# 12_WIFI_Module.net
KiCad netlist of a schematic drawn in Altium Designer
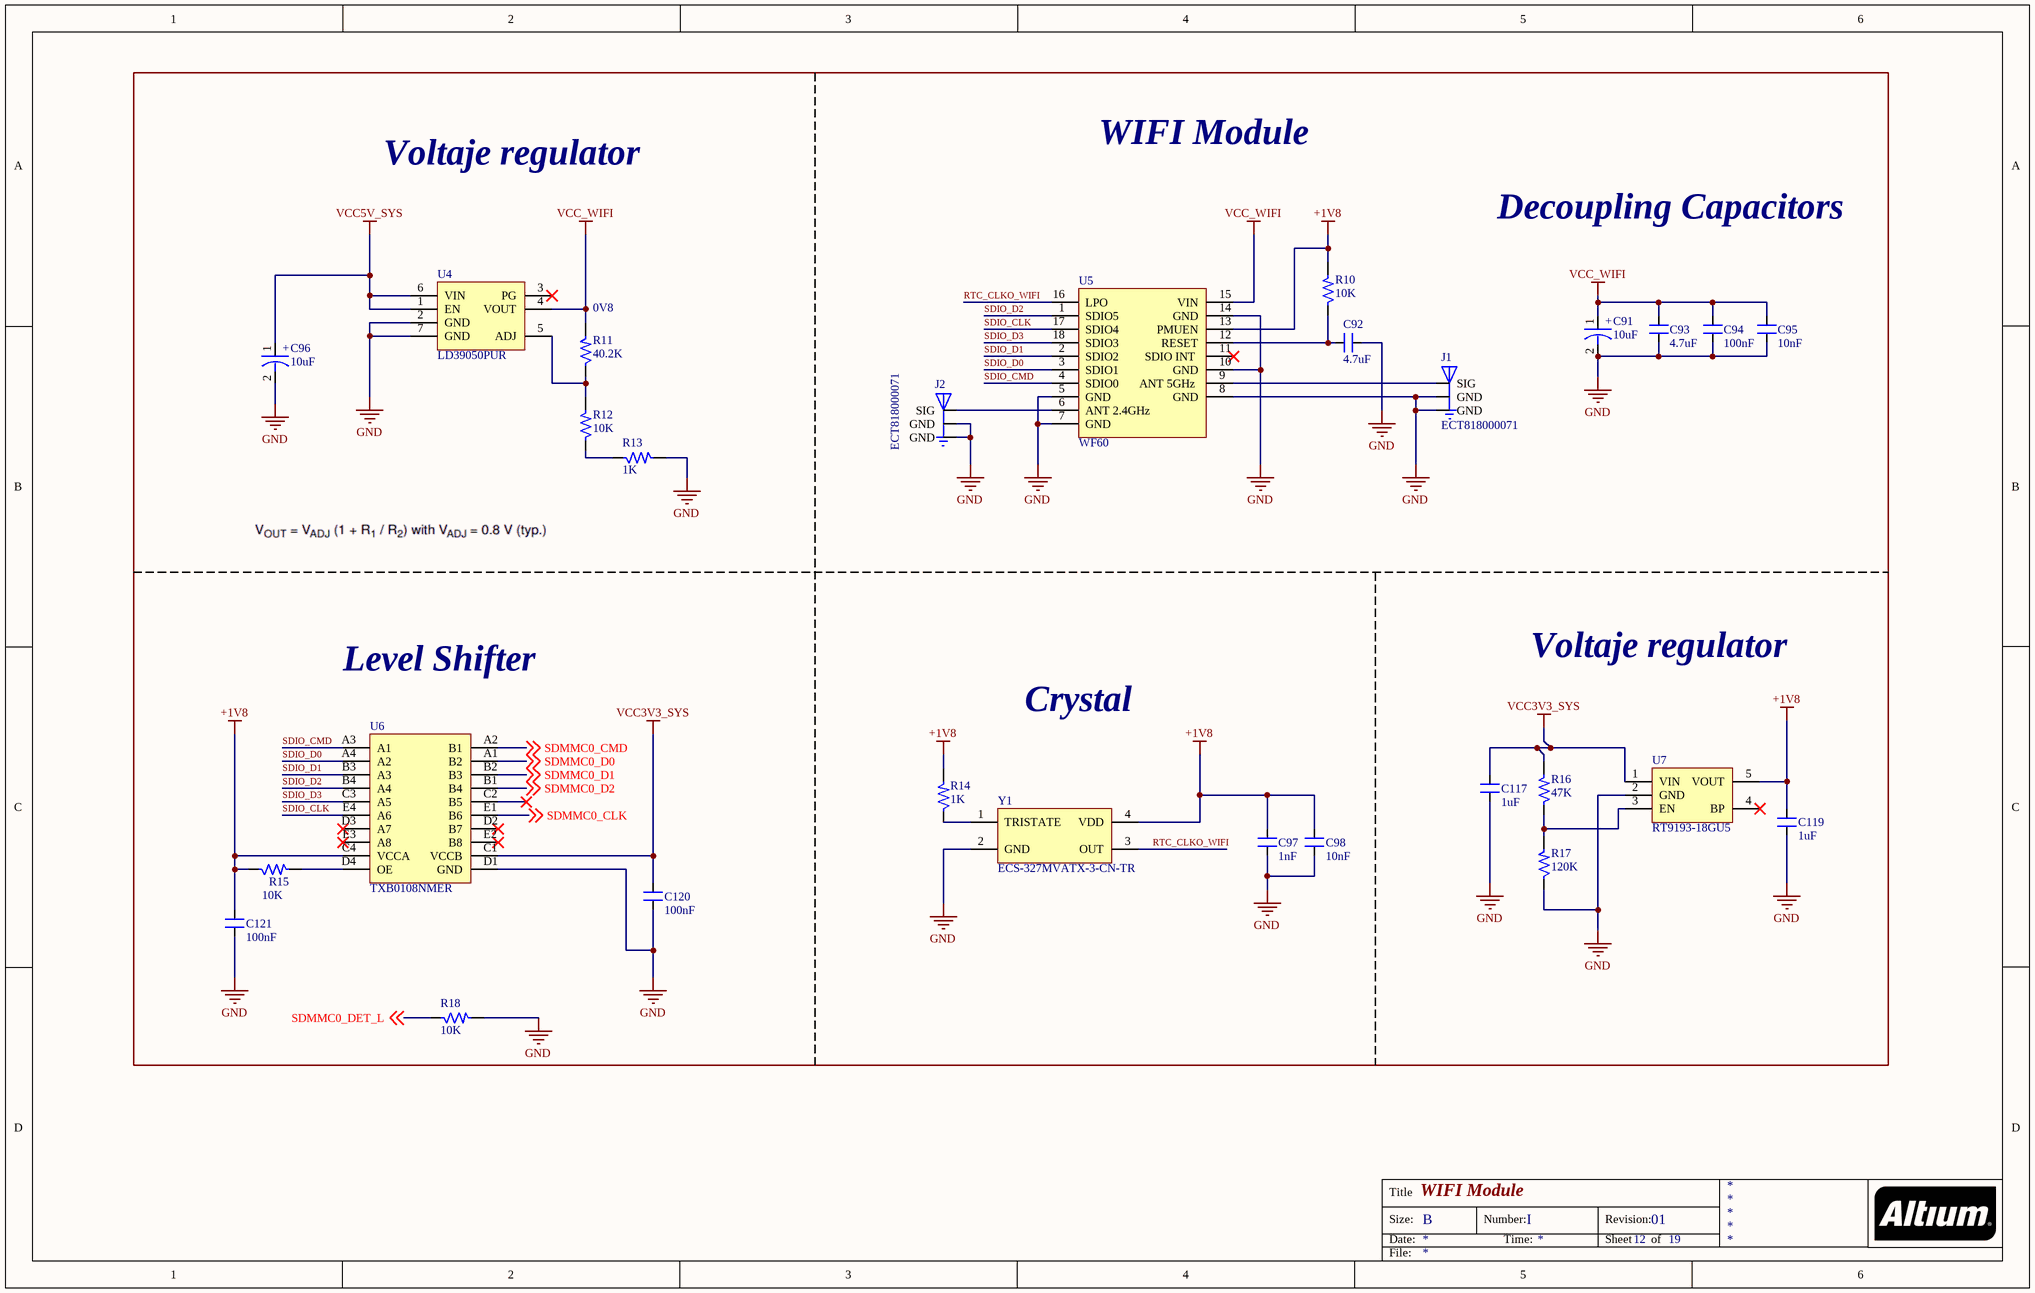
[diagram p0: [12] WIFI_Module.SchDoc]

(export (version "E")
  (design (tool "Eeschema 10.0.6"))
  (components
    (comp (ref "C91")
      (value "10uF")
      (footprint "CAP-T_1206")
      (description "10µF Molded Tantalum Capacitors 16V 1206 (3216 Metric) 3Ohm")
      (fields
        (field (name "MANUFACTURER") "AVX Corporation")
        (field (name "MANUFACTURER PART NUMBER") "TAJA106K016SNJ")
      )
      (libsource (lib "EsteemPCB_SOM_Course_intlib") (part "CAP-P_10uF-16V-10%-1206"))
    )
    (comp (ref "C92")
      (value "4.7uF")
      (footprint "CAP_0201")
      (description "4.7µF ±20% 6.3V Ceramic Capacitor X5R 0201 (0603 Metric)")
      (fields
        (field (name "MANUFACTURER") "Murata Electronics")
        (field (name "MANUFACTURER PART NUMBER") "GRM035R60J475ME15D")
      )
      (libsource (lib "EsteemPCB_SOM_Course_intlib") (part "CAP_4.7uF-6.3V-20%-0201"))
    )
    (comp (ref "C93")
      (value "4.7uF")
      (footprint "CAP_0402")
      (description "4.7µF ±10% 10V Ceramic Capacitor X5R 0402 (1005 Metric)")
      (fields
        (field (name "MANUFACTURER") "Samsung Electro-Mechanics")
        (field (name "MANUFACTURER PART NUMBER") "CL05A475KP5NRNC")
      )
      (libsource (lib "EsteemPCB_SOM_Course_intlib") (part "CAP_4.7uF-10V-10%-0402"))
    )
    (comp (ref "C94")
      (value "100nF")
      (footprint "CAP_0402")
      (description "0.1µF ±10% 25V Ceramic Capacitor X7R 0402 (1005 Metric)")
      (fields
        (field (name "MANUFACTURER") "Walsin Technology Corporation")
        (field (name "MANUFACTURER PART NUMBER") "0402B104K250CT")
      )
      (libsource (lib "EsteemPCB_SOM_Course_intlib") (part "CAP_100nF-25V-10%-0402"))
    )
    (comp (ref "C95")
      (value "10nF")
      (footprint "CAP_0402")
      (description "10000pF ±10% 10V Ceramic Capacitor X7R 0402 (1005 Metric)")
      (fields
        (field (name "MANUFACTURER") "AVX Corporation")
        (field (name "MANUFACTURER PART NUMBER") "0402ZC103KAT2A")
      )
      (libsource (lib "EsteemPCB_SOM_Course_intlib") (part "CAP_10nF-10V-10%-0402"))
    )
    (comp (ref "C96")
      (value "10uF")
      (footprint "CAP-T_1206")
      (description "10µF Molded Tantalum Capacitors 16V 1206 (3216 Metric) 3Ohm")
      (fields
        (field (name "MANUFACTURER") "AVX Corporation")
        (field (name "MANUFACTURER PART NUMBER") "TAJA106K016SNJ")
      )
      (libsource (lib "EsteemPCB_SOM_Course_intlib") (part "CAP-P_10uF-16V-10%-1206"))
    )
    (comp (ref "C97")
      (value "1nF")
      (footprint "CAP_0402")
      (description "1000pF ±10% 10V Ceramic Capacitor X7R 0402 (1005 Metric)")
      (fields
        (field (name "MANUFACTURER") "KEMET")
        (field (name "MANUFACTURER PART NUMBER") "C0402C102K8RACTU")
      )
      (libsource (lib "EsteemPCB_SOM_Course_intlib") (part "CAP_1nF-10V-10%-0402"))
    )
    (comp (ref "C98")
      (value "10nF")
      (footprint "CAP_0402")
      (description "10000pF ±10% 10V Ceramic Capacitor X7R 0402 (1005 Metric)")
      (fields
        (field (name "MANUFACTURER") "AVX Corporation")
        (field (name "MANUFACTURER PART NUMBER") "0402ZC103KAT2A")
      )
      (libsource (lib "EsteemPCB_SOM_Course_intlib") (part "CAP_10nF-10V-10%-0402"))
    )
    (comp (ref "C117")
      (value "1uF")
      (footprint "CAP_0201")
      (description "1µF ±20% 16V Ceramic Capacitor X5R 0201 (0603 Metric)")
      (fields
        (field (name "MANUFACTURER") "Samsung Electro-Mechanics")
        (field (name "MANUFACTURER PART NUMBER") "CL03A105MO3NRNH")
      )
      (libsource (lib "EsteemPCB_SOM_Course_intlib") (part "CAP_1uF-16V-10%-0201"))
    )
    (comp (ref "C119")
      (value "1uF")
      (footprint "CAP_0201")
      (description "1µF ±20% 16V Ceramic Capacitor X5R 0201 (0603 Metric)")
      (fields
        (field (name "MANUFACTURER") "Samsung Electro-Mechanics")
        (field (name "MANUFACTURER PART NUMBER") "CL03A105MO3NRNH")
      )
      (libsource (lib "EsteemPCB_SOM_Course_intlib") (part "CAP_1uF-16V-10%-0201"))
    )
    (comp (ref "C120")
      (value "100nF")
      (footprint "CAP_0201")
      (description "0.1µF ±10% 25V Ceramic Capacitor X5R 0201 (0603 Metric)")
      (fields
        (field (name "MANUFACTURER") "TDK Corporation")
        (field (name "MANUFACTURER PART NUMBER") "C0603X5R1E104K030BB")
      )
      (libsource (lib "EsteemPCB_SOM_Course_intlib") (part "CAP_100nF-25V-10%-0201"))
    )
    (comp (ref "C121")
      (value "100nF")
      (footprint "CAP_0201")
      (description "0.1µF ±10% 25V Ceramic Capacitor X5R 0201 (0603 Metric)")
      (fields
        (field (name "MANUFACTURER") "TDK Corporation")
        (field (name "MANUFACTURER PART NUMBER") "C0603X5R1E104K030BB")
      )
      (libsource (lib "EsteemPCB_SOM_Course_intlib") (part "CAP_100nF-25V-10%-0201"))
    )
    (comp (ref "J1")
      (value "ECT818000071")
      (footprint "CON3_UFL_116_SMD_ST")
      (description "SMD RF Connectors/Coaxial Connectors RoHS")
      (fields (field (name "MANUFACTURER") "ECT"))
      (libsource (lib "EsteemPCB_SOM_Course_intlib") (part "CON-PLG_3X1-ECT818000071-ST-SMD"))
    )
    (comp (ref "J2")
      (value "ECT818000071")
      (footprint "CON3_UFL_116_SMD_ST")
      (description "SMD RF Connectors/Coaxial Connectors RoHS")
      (fields (field (name "MANUFACTURER") "ECT"))
      (libsource (lib "EsteemPCB_SOM_Course_intlib") (part "CON-PLG_3X1-ECT818000071-ST-SMD"))
    )
    (comp (ref "R10")
      (value "10K")
      (footprint "RES_0201")
      (description "10 kOhms ±1% 0.05W, 1/20W Chip Resistor 0201 (0603 Metric) Thick Film")
      (fields
        (field (name "MANUFACTURER") "Stackpole Electronics Inc")
        (field (name "MANUFACTURER PART NUMBER") "RMCF0201FT10K0")
      )
      (libsource (lib "EsteemPCB_SOM_Course_intlib") (part "RES_10K-0.05W-1%-0201"))
    )
    (comp (ref "R11")
      (value "40.2K")
      (footprint "RES_0201")
      (fields
        (field (name "MANUFACTURER") "Yageo")
        (field (name "MANUFACTURER PART NUMBER") "AC0201FR-0740K2L")
      )
      (libsource (lib "EsteemPCB_SOM_Course_intlib") (part "RES_40.2K-0.05W-1%-0201"))
    )
    (comp (ref "R12")
      (value "10K")
      (footprint "RES_0201")
      (description "10 kOhms ±1% 0.05W, 1/20W Chip Resistor 0201 (0603 Metric) Thick Film")
      (fields
        (field (name "MANUFACTURER") "Stackpole Electronics Inc")
        (field (name "MANUFACTURER PART NUMBER") "RMCF0201FT10K0")
      )
      (libsource (lib "EsteemPCB_SOM_Course_intlib") (part "RES_10K-0.05W-1%-0201"))
    )
    (comp (ref "R13")
      (value "1K")
      (footprint "RES_0402")
      (description "1 kOhms ±1% 0.1W, 1/10W Chip Resistor 0402 (1005 Metric) Anti-Sulfur Thin Film")
      (fields
        (field (name "MANUFACTURER") "Vishay Beyschlag/Draloric/BC Components")
        (field (name "MANUFACTURER PART NUMBER") "MCS04020C1001FE000")
      )
      (libsource (lib "EsteemPCB_SOM_Course_intlib") (part "RES_1K-0.1W-1%-0402"))
    )
    (comp (ref "R14")
      (value "1K")
      (footprint "RES_0201")
      (description "10 kOhms ±1% 0.05W, 1/20W Chip Resistor 0201 (0603 Metric) Thick Film")
      (fields
        (field (name "MANUFACTURER") "Stackpole Electronics Inc")
        (field (name "MANUFACTURER PART NUMBER") "RMCF0201FT10K0")
      )
      (libsource (lib "EsteemPCB_SOM_Course_intlib") (part "RES_10K-0.05W-1%-0201"))
    )
    (comp (ref "R15")
      (value "10K")
      (footprint "RES_0201")
      (description "10 kOhms ±1% 0.05W, 1/20W Chip Resistor 0201 (0603 Metric) Thick Film")
      (fields
        (field (name "MANUFACTURER") "Stackpole Electronics Inc")
        (field (name "MANUFACTURER PART NUMBER") "RMCF0201FT10K0")
      )
      (libsource (lib "EsteemPCB_SOM_Course_intlib") (part "RES_10K-0.05W-1%-0201"))
    )
    (comp (ref "R16")
      (value "47K")
      (footprint "RES_0402")
      (description "47 kOhms ±1% 0.1W, 1/10W Chip Resistor 0402 (1005 Metric) Automotive AEC-Q200 Thick Film")
      (fields
        (field (name "MANUFACTURER") "Panasonic Electronic Components")
        (field (name "MANUFACTURER PART NUMBER") "ERJ-2RKF4702X")
      )
      (libsource (lib "EsteemPCB_SOM_Course_intlib") (part "RES_47K-0.1W-1%-0402"))
    )
    (comp (ref "R17")
      (value "120K")
      (footprint "RES_0402")
      (description "120 kOhms ±1% 0.1W, 1/10W Chip Resistor 0402 (1005 Metric) Anti-Sulfur Thin Film")
      (fields
        (field (name "MANUFACTURER") "Vishay Beyschlag/Draloric/BC Components")
        (field (name "MANUFACTURER PART NUMBER") "MCS04020C1203FE000")
      )
      (libsource (lib "EsteemPCB_SOM_Course_intlib") (part "RES_120K-0.1W-1%-0402"))
    )
    (comp (ref "R18")
      (value "10K")
      (footprint "RES_0201")
      (description "10 kOhms ±1% 0.05W, 1/20W Chip Resistor 0201 (0603 Metric) Thick Film")
      (fields
        (field (name "MANUFACTURER") "Stackpole Electronics Inc")
        (field (name "MANUFACTURER PART NUMBER") "RMCF0201FT10K0")
      )
      (libsource (lib "EsteemPCB_SOM_Course_intlib") (part "RES_10K-0.05W-1%-0201"))
    )
    (comp (ref "U4")
      (value "LD39050PUR")
      (footprint "DFN-6_37.4_165_33X15_SMD")
      (description "Adjustable 5.5V 0.8V 500mA DFN-6 Linear Voltage Regulators RoHS")
      (fields (field (name "MANUFACTURER") "STMicroelectronics"))
      (libsource (lib "EsteemPCB_SOM_Course_intlib") (part "REG_5.5V-0~5.1V-0.5A-2.55W-DFN-6"))
    )
    (comp (ref "U5")
      (value "WF60")
      (footprint "MOD_WF60")
      (description "Amp’ed RF Tech presents the WF60 WiFi dual\r\nband module: 802.11abgn.")
      (fields (field (name "MANUFACTURER") "Amp’ed"))
      (libsource (lib "EsteemPCB_SOM_Course_intlib") (part "MOD_WF60-SMD"))
    )
    (comp (ref "U6")
      (value "TXB0108NMER")
      (footprint "NFBGA_31.4_125.9X102.36")
      (fields (field (name "MANUFACTURER") "Texas Instruments"))
      (libsource (lib "EsteemPCB_SOM_Course_intlib") (part "IC_TXB0108NMER"))
    )
    (comp (ref "U7")
      (value "RT9193-18GU5")
      (footprint "SC70-5")
      (description "Linear Voltage Regulator IC 1 Output 300mA SC-70-5")
      (fields (field (name "MANUFACTURER") "Richtek USA Inc."))
      (libsource (lib "EsteemPCB_SOM_Course_intlib") (part "REG_1.8V-300mA-5.5V-SC70-5"))
    )
    (comp (ref "Y1")
      (value "ECS-327MVATX-3-CN-TR")
      (footprint "XTAL_57_35X31_SMD")
      (description "32.768kHz XO (Standard) CMOS Oscillator 1.6V ~ 3.6V Enable/Disable 4-SMD, No Lead")
      (fields (field (name "MANUFACTURER") "ECS INC"))
      (libsource (lib "EsteemPCB_SOM_Course_intlib") (part "XTAL_ECS-327MVATX-2-CN-TR"))
    )
  )
  (nets
    (net (code "1") (name "+1V8") (class "Default")
      (node (ref "C119") (pin "2") (pinfunction "2_2") (pintype "passive"))
      (node (ref "C121") (pin "2") (pinfunction "2_2") (pintype "passive"))
      (node (ref "C97") (pin "2") (pinfunction "2_2") (pintype "passive"))
      (node (ref "C98") (pin "2") (pinfunction "2_2") (pintype "passive"))
      (node (ref "R10") (pin "2") (pinfunction "2_2") (pintype "passive"))
      (node (ref "R14") (pin "2") (pinfunction "2_2") (pintype "passive"))
      (node (ref "R15") (pin "1") (pinfunction "1_1") (pintype "passive"))
      (node (ref "U5") (pin "13") (pinfunction "PMUEN_13") (pintype "passive"))
      (node (ref "U6") (pin "C4") (pinfunction "VCCA_C4") (pintype "passive"))
      (node (ref "U7") (pin "5") (pinfunction "VOUT_5") (pintype "passive"))
      (node (ref "Y1") (pin "4") (pinfunction "VDD_4") (pintype "passive"))
    )
    (net (code "2") (name "/RTC_CLKO_WIFI") (class "Default")
      (node (ref "U5") (pin "16") (pinfunction "LPO_16") (pintype "passive"))
      (node (ref "Y1") (pin "3") (pinfunction "OUT_3") (pintype "passive"))
    )
    (net (code "3") (name "/SDIO_CLK") (class "Default")
      (node (ref "U5") (pin "17") (pinfunction "SDIO4_17") (pintype "passive"))
      (node (ref "U6") (pin "E4") (pinfunction "A6_E4") (pintype "passive"))
    )
    (net (code "4") (name "/SDIO_CMD") (class "Default")
      (node (ref "U5") (pin "4") (pinfunction "SDIO0_4") (pintype "passive"))
      (node (ref "U6") (pin "A3") (pinfunction "A1_A3") (pintype "passive"))
    )
    (net (code "5") (name "/SDIO_D0") (class "Default")
      (node (ref "U5") (pin "3") (pinfunction "SDIO1_3") (pintype "passive"))
      (node (ref "U6") (pin "A4") (pinfunction "A2_A4") (pintype "passive"))
    )
    (net (code "6") (name "/SDIO_D1") (class "Default")
      (node (ref "U5") (pin "2") (pinfunction "SDIO2_2") (pintype "passive"))
      (node (ref "U6") (pin "B3") (pinfunction "A3_B3") (pintype "passive"))
    )
    (net (code "7") (name "/SDIO_D2") (class "Default")
      (node (ref "U5") (pin "1") (pinfunction "SDIO5_1") (pintype "passive"))
      (node (ref "U6") (pin "B4") (pinfunction "A4_B4") (pintype "passive"))
    )
    (net (code "8") (name "/SDIO_D3") (class "Default")
      (node (ref "U5") (pin "18") (pinfunction "SDIO3_18") (pintype "passive"))
      (node (ref "U6") (pin "C3") (pinfunction "A5_C3") (pintype "passive"))
    )
    (net (code "9") (name "GND") (class "Default")
      (node (ref "C117") (pin "1") (pinfunction "1_1") (pintype "passive"))
      (node (ref "C119") (pin "1") (pinfunction "1_1") (pintype "passive"))
      (node (ref "C120") (pin "1") (pinfunction "1_1") (pintype "passive"))
      (node (ref "C121") (pin "1") (pinfunction "1_1") (pintype "passive"))
      (node (ref "C91") (pin "2") (pinfunction "2_2") (pintype "passive"))
      (node (ref "C92") (pin "2") (pinfunction "2_2") (pintype "passive"))
      (node (ref "C93") (pin "1") (pinfunction "1_1") (pintype "passive"))
      (node (ref "C94") (pin "1") (pinfunction "1_1") (pintype "passive"))
      (node (ref "C95") (pin "1") (pinfunction "1_1") (pintype "passive"))
      (node (ref "C96") (pin "2") (pinfunction "2_2") (pintype "passive"))
      (node (ref "C97") (pin "1") (pinfunction "1_1") (pintype "passive"))
      (node (ref "C98") (pin "1") (pinfunction "1_1") (pintype "passive"))
      (node (ref "J1") (pin "1") (pinfunction "GND_1") (pintype "passive"))
      (node (ref "J1") (pin "3") (pinfunction "GND_3") (pintype "passive"))
      (node (ref "J2") (pin "1") (pinfunction "GND_1") (pintype "passive"))
      (node (ref "J2") (pin "3") (pinfunction "GND_3") (pintype "passive"))
      (node (ref "R13") (pin "2") (pinfunction "2_2") (pintype "passive"))
      (node (ref "R17") (pin "1") (pinfunction "1_1") (pintype "passive"))
      (node (ref "R18") (pin "2") (pinfunction "2_2") (pintype "passive"))
      (node (ref "U4") (pin "2") (pinfunction "GND_2") (pintype "passive"))
      (node (ref "U4") (pin "7") (pinfunction "GND_7") (pintype "passive"))
      (node (ref "U5") (pin "10") (pinfunction "GND_10") (pintype "passive"))
      (node (ref "U5") (pin "14") (pinfunction "GND_14") (pintype "passive"))
      (node (ref "U5") (pin "5") (pinfunction "GND_5") (pintype "passive"))
      (node (ref "U5") (pin "7") (pinfunction "GND_7") (pintype "passive"))
      (node (ref "U5") (pin "8") (pinfunction "GND_8") (pintype "passive"))
      (node (ref "U6") (pin "D1") (pinfunction "GND_D1") (pintype "passive"))
      (node (ref "U7") (pin "2") (pinfunction "GND_2") (pintype "passive"))
      (node (ref "Y1") (pin "2") (pinfunction "GND_2") (pintype "passive"))
    )
    (net (code "10") (name "Net-(J1-SIG)") (class "Default")
      (node (ref "J1") (pin "2") (pinfunction "SIG_2") (pintype "passive"))
      (node (ref "U5") (pin "9") (pinfunction "ANT_5GHz_9") (pintype "passive"))
    )
    (net (code "11") (name "Net-(J2-SIG)") (class "Default")
      (node (ref "J2") (pin "2") (pinfunction "SIG_2") (pintype "passive"))
      (node (ref "U5") (pin "6") (pinfunction "ANT_2.4GHz_6") (pintype "passive"))
    )
    (net (code "12") (name "Net-(R12-Pad1)") (class "Default")
      (node (ref "R12") (pin "1") (pinfunction "1_1") (pintype "passive"))
      (node (ref "R13") (pin "1") (pinfunction "1_1") (pintype "passive"))
    )
    (net (code "13") (name "Net-(U4-ADJ)") (class "Default")
      (node (ref "R11") (pin "1") (pinfunction "1_1") (pintype "passive"))
      (node (ref "R12") (pin "2") (pinfunction "2_2") (pintype "passive"))
      (node (ref "U4") (pin "5") (pinfunction "ADJ_5") (pintype "passive"))
    )
    (net (code "14") (name "Net-(U5-RESET)") (class "Default")
      (node (ref "C92") (pin "1") (pinfunction "1_1") (pintype "passive"))
      (node (ref "R10") (pin "1") (pinfunction "1_1") (pintype "passive"))
      (node (ref "U5") (pin "12") (pinfunction "RESET_12") (pintype "passive"))
    )
    (net (code "15") (name "Net-(U6-OE)") (class "Default")
      (node (ref "R15") (pin "2") (pinfunction "2_2") (pintype "passive"))
      (node (ref "U6") (pin "D4") (pinfunction "OE_D4") (pintype "passive"))
    )
    (net (code "16") (name "Net-(U7-EN)") (class "Default")
      (node (ref "R16") (pin "1") (pinfunction "1_1") (pintype "passive"))
      (node (ref "R17") (pin "2") (pinfunction "2_2") (pintype "passive"))
      (node (ref "U7") (pin "3") (pinfunction "EN_3") (pintype "passive"))
    )
    (net (code "17") (name "Net-(Y1-TRISTATE)") (class "Default")
      (node (ref "R14") (pin "1") (pinfunction "1_1") (pintype "passive"))
      (node (ref "Y1") (pin "1") (pinfunction "TRISTATE_1") (pintype "passive"))
    )
    (net (code "18") (name "SDMMC0_CLK") (class "Default")
      (node (ref "U6") (pin "E1") (pinfunction "B6_E1") (pintype "passive"))
    )
    (net (code "19") (name "SDMMC0_CMD") (class "Default")
      (node (ref "U6") (pin "A2") (pinfunction "B1_A2") (pintype "passive"))
    )
    (net (code "20") (name "SDMMC0_D0") (class "Default")
      (node (ref "U6") (pin "A1") (pinfunction "B2_A1") (pintype "passive"))
    )
    (net (code "21") (name "SDMMC0_D1") (class "Default")
      (node (ref "U6") (pin "B2") (pinfunction "B3_B2") (pintype "passive"))
    )
    (net (code "22") (name "SDMMC0_D2") (class "Default")
      (node (ref "U6") (pin "B1") (pinfunction "B4_B1") (pintype "passive"))
    )
    (net (code "23") (name "SDMMC0_DET_L") (class "Default")
      (node (ref "R18") (pin "1") (pinfunction "1_1") (pintype "passive"))
    )
    (net (code "24") (name "VCC3V3_SYS") (class "Default")
      (node (ref "C117") (pin "2") (pinfunction "2_2") (pintype "passive"))
      (node (ref "C120") (pin "2") (pinfunction "2_2") (pintype "passive"))
      (node (ref "R16") (pin "2") (pinfunction "2_2") (pintype "passive"))
      (node (ref "U6") (pin "C1") (pinfunction "VCCB_C1") (pintype "passive"))
      (node (ref "U7") (pin "1") (pinfunction "VIN_1") (pintype "passive"))
    )
    (net (code "25") (name "VCC5V_SYS") (class "Default")
      (node (ref "C96") (pin "1") (pinfunction "1_1") (pintype "passive"))
      (node (ref "U4") (pin "1") (pinfunction "EN_1") (pintype "passive"))
      (node (ref "U4") (pin "6") (pinfunction "VIN_6") (pintype "passive"))
    )
    (net (code "26") (name "VCC_WIFI") (class "Default")
      (node (ref "C91") (pin "1") (pinfunction "1_1") (pintype "passive"))
      (node (ref "C93") (pin "2") (pinfunction "2_2") (pintype "passive"))
      (node (ref "C94") (pin "2") (pinfunction "2_2") (pintype "passive"))
      (node (ref "C95") (pin "2") (pinfunction "2_2") (pintype "passive"))
      (node (ref "R11") (pin "2") (pinfunction "2_2") (pintype "passive"))
      (node (ref "U4") (pin "4") (pinfunction "VOUT_4") (pintype "passive"))
      (node (ref "U5") (pin "15") (pinfunction "VIN_15") (pintype "passive"))
    )
    (net (code "27") (name "unconnected-(U4-PG-Pad3)") (class "Default")
      (node (ref "U4") (pin "3") (pinfunction "PG_3") (pintype "passive+no_connect"))
    )
    (net (code "28") (name "unconnected-(U5-SDIO_INT-Pad11)") (class "Default")
      (node (ref "U5") (pin "11") (pinfunction "SDIO_INT_11") (pintype "passive+no_connect"))
    )
    (net (code "29") (name "unconnected-(U6-A7-PadD3)") (class "Default")
      (node (ref "U6") (pin "D3") (pinfunction "A7_D3") (pintype "passive+no_connect"))
    )
    (net (code "30") (name "unconnected-(U6-A8-PadE3)") (class "Default")
      (node (ref "U6") (pin "E3") (pinfunction "A8_E3") (pintype "passive+no_connect"))
    )
    (net (code "31") (name "unconnected-(U6-B5-PadC2)") (class "Default")
      (node (ref "U6") (pin "C2") (pinfunction "B5_C2") (pintype "passive+no_connect"))
    )
    (net (code "32") (name "unconnected-(U6-B7-PadD2)") (class "Default")
      (node (ref "U6") (pin "D2") (pinfunction "B7_D2") (pintype "passive+no_connect"))
    )
    (net (code "33") (name "unconnected-(U6-B8-PadE2)") (class "Default")
      (node (ref "U6") (pin "E2") (pinfunction "B8_E2") (pintype "passive+no_connect"))
    )
    (net (code "34") (name "unconnected-(U7-BP-Pad4)") (class "Default")
      (node (ref "U7") (pin "4") (pinfunction "BP_4") (pintype "passive+no_connect"))
    )
  )
)
